# remote-connection-board.net
KiCad netlist of a schematic drawn in EAGLE
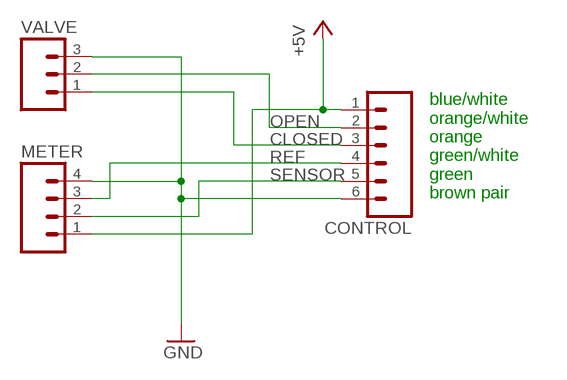
[diagram p0: schematic, sheet 1]

(export (version "E")
  (design (tool "Eeschema 10.0.6"))
  (components
    (comp (ref "CONTROL")
      (value "M06")
      (footprint "eagle-import:06P")
      (libsource (lib "eagle-import") (part "M06"))
    )
    (comp (ref "METER")
      (value "M04")
      (footprint "eagle-import:04P")
      (libsource (lib "eagle-import") (part "M04"))
    )
    (comp (ref "VALVE")
      (value "M03")
      (footprint "eagle-import:03P")
      (libsource (lib "eagle-import") (part "M03"))
    )
  )
  (nets
    (net (code "1") (name "+5V") (class "Default")
      (node (ref "CONTROL") (pin "1") (pinfunction "1_1") (pintype "passive"))
      (node (ref "METER") (pin "1") (pinfunction "1_1") (pintype "passive"))
    )
    (net (code "2") (name "/CLOSED") (class "Default")
      (node (ref "CONTROL") (pin "3") (pinfunction "3_3") (pintype "passive"))
      (node (ref "VALVE") (pin "1") (pinfunction "1_1") (pintype "passive"))
    )
    (net (code "3") (name "/OPEN") (class "Default")
      (node (ref "CONTROL") (pin "2") (pinfunction "2_2") (pintype "passive"))
      (node (ref "VALVE") (pin "2") (pinfunction "2_2") (pintype "passive"))
    )
    (net (code "4") (name "/REF") (class "Default")
      (node (ref "CONTROL") (pin "4") (pinfunction "4_4") (pintype "passive"))
      (node (ref "METER") (pin "3") (pinfunction "3_3") (pintype "passive"))
    )
    (net (code "5") (name "/SENSOR") (class "Default")
      (node (ref "CONTROL") (pin "5") (pinfunction "5_5") (pintype "passive"))
      (node (ref "METER") (pin "2") (pinfunction "2_2") (pintype "passive"))
    )
    (net (code "6") (name "GND") (class "Default")
      (node (ref "CONTROL") (pin "6") (pinfunction "6_6") (pintype "passive"))
      (node (ref "METER") (pin "4") (pinfunction "4_4") (pintype "passive"))
      (node (ref "VALVE") (pin "3") (pinfunction "3_3") (pintype "passive"))
    )
  )
)
